# ASD2501.net
KiCad netlist of a schematic drawn in EAGLE
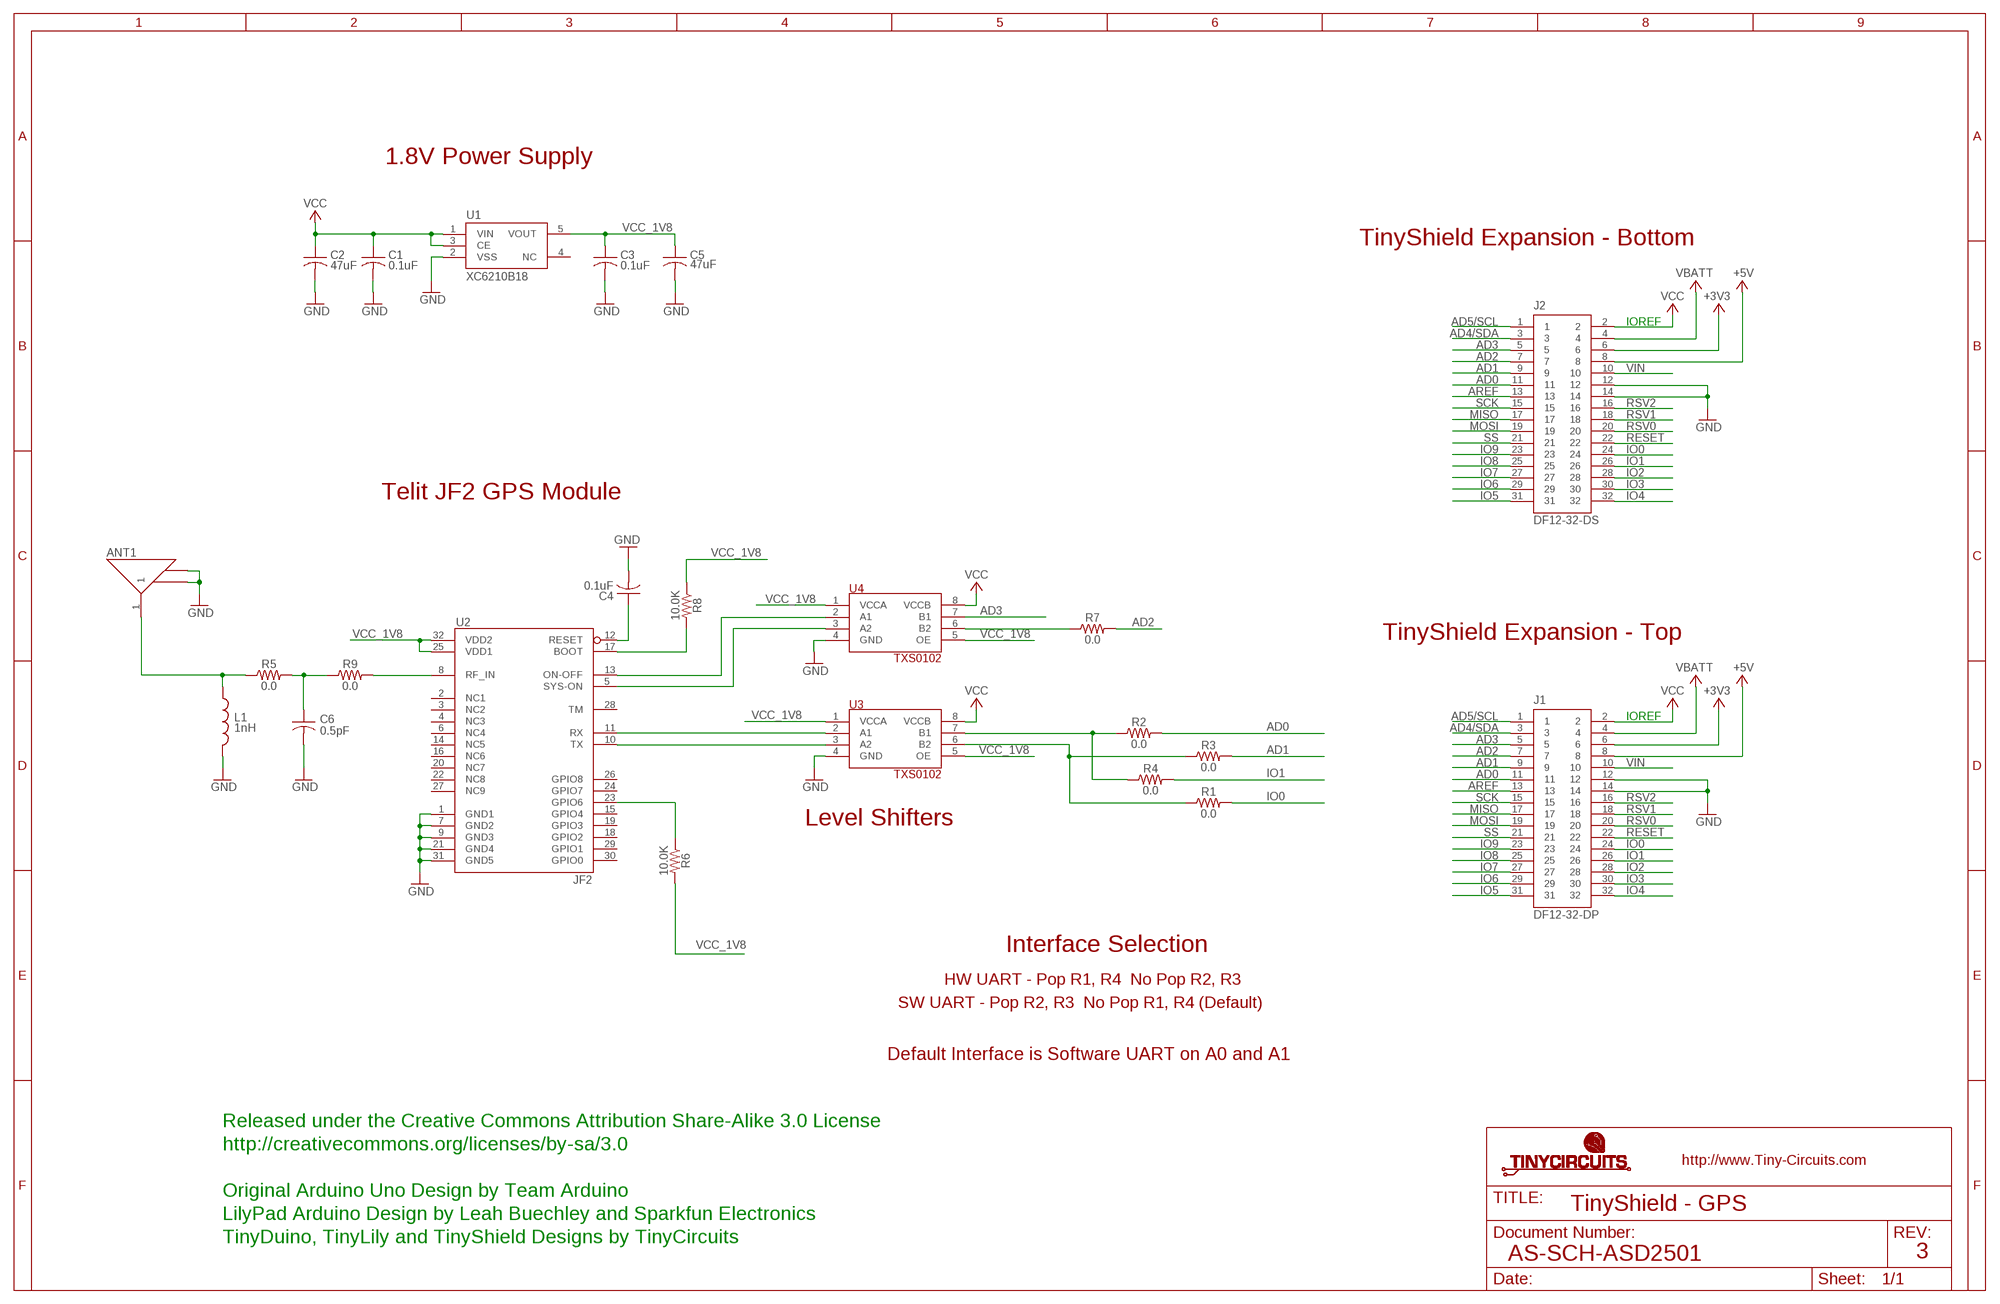
[diagram p0: schematic, sheet 1]

(export (version "E")
  (design (tool "Eeschema 10.0.6"))
  (components
    (comp (ref "ANT1")
      (value "AS-ITM-00109")
      (footprint "eagle-import:W3011")
      (libsource (lib "eagle-import") (part "AS-ITM-00109"))
    )
    (comp (ref "C1")
      (value "0.1uF")
      (footprint "eagle-import:C0402")
      (fields (field (name "PARTNO") "AS-ITM-00008") (field (name "PARTNO_1") "AS-ITM-00008"))
      (libsource (lib "eagle-import") (part "AS-ITM-00008"))
    )
    (comp (ref "C2")
      (value "47uF")
      (footprint "eagle-import:C1206")
      (fields (field (name "PARTNUM") "AS-ITM-00049") (field (name "PARTNUM_1") "AS-ITM-00049"))
      (libsource (lib "eagle-import") (part "AS-ITM-00049"))
    )
    (comp (ref "C3")
      (value "0.1uF")
      (footprint "eagle-import:C0402")
      (fields (field (name "PARTNO") "AS-ITM-00008") (field (name "PARTNO_1") "AS-ITM-00008"))
      (libsource (lib "eagle-import") (part "AS-ITM-00008"))
    )
    (comp (ref "C4")
      (value "0.1uF")
      (footprint "eagle-import:C0402")
      (fields (field (name "PARTNO") "AS-ITM-00008") (field (name "PARTNO_1") "AS-ITM-00008"))
      (libsource (lib "eagle-import") (part "AS-ITM-00008"))
    )
    (comp (ref "C5")
      (value "47uF")
      (footprint "eagle-import:C1206")
      (fields (field (name "PARTNUM") "AS-ITM-00049"))
      (libsource (lib "eagle-import") (part "AS-ITM-00049"))
    )
    (comp (ref "C6")
      (value "0.5pF")
      (footprint "eagle-import:C0402")
      (libsource (lib "eagle-import") (part "AS-ITM-00126"))
    )
    (comp (ref "J1")
      (value "DF12-32-DP")
      (footprint "eagle-import:DF12-32-DP")
      (fields (field (name "PARTNO") "AS-ITM-00015") (field (name "PARTNO_1") "AS-ITM-00015"))
      (libsource (lib "eagle-import") (part "AS-ITM-00015"))
    )
    (comp (ref "J2")
      (value "DF12-32-DS")
      (footprint "eagle-import:DF12-32-DS")
      (fields (field (name "PARTNO") "AS-ITM-00012") (field (name "PARTNO_1") "AS-ITM-00012"))
      (libsource (lib "eagle-import") (part "AS-ITM-00012"))
    )
    (comp (ref "L1")
      (value "1nH")
      (footprint "eagle-import:0402")
      (libsource (lib "eagle-import") (part "AS-ITM-00127"))
    )
    (comp (ref "R1")
      (value "0.0")
      (footprint "eagle-import:0402")
      (fields (field (name "PARTNO") "AS-ITM-00076"))
      (libsource (lib "eagle-import") (part "AS-ITM-00076"))
    )
    (comp (ref "R2")
      (value "0.0")
      (footprint "eagle-import:0402_SHORT")
      (libsource (lib "eagle-import") (part "AS-ITM-000760402_SHORT"))
    )
    (comp (ref "R3")
      (value "0.0")
      (footprint "eagle-import:0402_SHORT")
      (libsource (lib "eagle-import") (part "AS-ITM-000760402_SHORT"))
    )
    (comp (ref "R4")
      (value "0.0")
      (footprint "eagle-import:0402")
      (fields (field (name "PARTNO") "AS-ITM-00076"))
      (libsource (lib "eagle-import") (part "AS-ITM-00076"))
    )
    (comp (ref "R5")
      (value "0.0")
      (footprint "eagle-import:0402")
      (fields (field (name "PARTNO") "AS-ITM-00076"))
      (libsource (lib "eagle-import") (part "AS-ITM-00076"))
    )
    (comp (ref "R6")
      (value "10.0K")
      (footprint "eagle-import:0402")
      (fields (field (name "PARTNO") "AS-ITM-00032"))
      (libsource (lib "eagle-import") (part "AS-ITM-00032"))
    )
    (comp (ref "R7")
      (value "0.0")
      (footprint "eagle-import:0402")
      (fields (field (name "PARTNO") "AS-ITM-00076") (field (name "PARTNO_1") "AS-ITM-00076"))
      (libsource (lib "eagle-import") (part "AS-ITM-00076"))
    )
    (comp (ref "R8")
      (value "10.0K")
      (footprint "eagle-import:0402")
      (fields (field (name "PARTNO") "AS-ITM-00032") (field (name "PARTNO_1") "AS-ITM-00032"))
      (libsource (lib "eagle-import") (part "AS-ITM-00032"))
    )
    (comp (ref "R9")
      (value "0.0")
      (footprint "eagle-import:0402")
      (fields (field (name "PARTNO") "AS-ITM-00076"))
      (libsource (lib "eagle-import") (part "AS-ITM-00076"))
    )
    (comp (ref "U1")
      (value "XC6210B18")
      (footprint "eagle-import:SOT-25")
      (fields (field (name "PARTNO") "AS-ITM-00075") (field (name "PARTNO_1") "AS-ITM-00075"))
      (libsource (lib "eagle-import") (part "AS-ITM-00075"))
    )
    (comp (ref "U2")
      (value "JF2")
      (footprint "eagle-import:JF2")
      (fields (field (name "PARTNO") "AS-ITM-00077"))
      (libsource (lib "eagle-import") (part "AS-ITM-00077"))
    )
    (comp (ref "U3")
      (value "TXS0102")
      (footprint "eagle-import:DQE(R-PX2SON-N8)")
      (fields (field (name "PARTNO") "AS-ITM-00073"))
      (libsource (lib "eagle-import") (part "AS-ITM-00073"))
    )
    (comp (ref "U4")
      (value "TXS0102")
      (footprint "eagle-import:DQE(R-PX2SON-N8)")
      (fields (field (name "PARTNO") "AS-ITM-00073") (field (name "PARTNO_1") "AS-ITM-00073"))
      (libsource (lib "eagle-import") (part "AS-ITM-00073"))
    )
  )
  (nets
    (net (code "1") (name "+3V3") (class "Default")
      (node (ref "J1") (pin "6") (pinfunction "6_6") (pintype "bidirectional"))
      (node (ref "J2") (pin "6") (pinfunction "6_6") (pintype "bidirectional"))
    )
    (net (code "2") (name "+5V") (class "Default")
      (node (ref "J1") (pin "8") (pinfunction "8_8") (pintype "bidirectional"))
      (node (ref "J2") (pin "8") (pinfunction "8_8") (pintype "bidirectional"))
    )
    (net (code "3") (name "/AD0") (class "Default")
      (node (ref "J1") (pin "11") (pinfunction "11_11") (pintype "bidirectional"))
      (node (ref "J2") (pin "11") (pinfunction "11_11") (pintype "bidirectional"))
      (node (ref "R2") (pin "2") (pinfunction "2_2") (pintype "passive"))
    )
    (net (code "4") (name "/AD1") (class "Default")
      (node (ref "J1") (pin "9") (pinfunction "9_9") (pintype "bidirectional"))
      (node (ref "J2") (pin "9") (pinfunction "9_9") (pintype "bidirectional"))
      (node (ref "R3") (pin "2") (pinfunction "2_2") (pintype "passive"))
    )
    (net (code "5") (name "/AD2") (class "Default")
      (node (ref "J1") (pin "7") (pinfunction "7_7") (pintype "bidirectional"))
      (node (ref "J2") (pin "7") (pinfunction "7_7") (pintype "bidirectional"))
      (node (ref "R7") (pin "2") (pinfunction "2_2") (pintype "passive"))
    )
    (net (code "6") (name "/AD3") (class "Default")
      (node (ref "J1") (pin "5") (pinfunction "5_5") (pintype "bidirectional"))
      (node (ref "J2") (pin "5") (pinfunction "5_5") (pintype "bidirectional"))
      (node (ref "U4") (pin "7") (pinfunction "B1_7") (pintype "bidirectional"))
    )
    (net (code "7") (name "/AD4{slash}SDA") (class "Default")
      (node (ref "J1") (pin "3") (pinfunction "3_3") (pintype "bidirectional"))
      (node (ref "J2") (pin "3") (pinfunction "3_3") (pintype "bidirectional"))
    )
    (net (code "8") (name "/AD5{slash}SCL") (class "Default")
      (node (ref "J1") (pin "1") (pinfunction "1_1") (pintype "bidirectional"))
      (node (ref "J2") (pin "1") (pinfunction "1_1") (pintype "bidirectional"))
    )
    (net (code "9") (name "/AREF") (class "Default")
      (node (ref "J1") (pin "13") (pinfunction "13_13") (pintype "bidirectional"))
      (node (ref "J2") (pin "13") (pinfunction "13_13") (pintype "bidirectional"))
    )
    (net (code "10") (name "/IO0") (class "Default")
      (node (ref "J1") (pin "24") (pinfunction "24_24") (pintype "bidirectional"))
      (node (ref "J2") (pin "24") (pinfunction "24_24") (pintype "bidirectional"))
      (node (ref "R1") (pin "2") (pinfunction "2_2") (pintype "passive"))
    )
    (net (code "11") (name "/IO1") (class "Default")
      (node (ref "J1") (pin "26") (pinfunction "26_26") (pintype "bidirectional"))
      (node (ref "J2") (pin "26") (pinfunction "26_26") (pintype "bidirectional"))
      (node (ref "R4") (pin "2") (pinfunction "2_2") (pintype "passive"))
    )
    (net (code "12") (name "/IO2") (class "Default")
      (node (ref "J1") (pin "28") (pinfunction "28_28") (pintype "bidirectional"))
      (node (ref "J2") (pin "28") (pinfunction "28_28") (pintype "bidirectional"))
    )
    (net (code "13") (name "/IO3") (class "Default")
      (node (ref "J1") (pin "30") (pinfunction "30_30") (pintype "bidirectional"))
      (node (ref "J2") (pin "30") (pinfunction "30_30") (pintype "bidirectional"))
    )
    (net (code "14") (name "/IO4") (class "Default")
      (node (ref "J1") (pin "32") (pinfunction "32_32") (pintype "bidirectional"))
      (node (ref "J2") (pin "32") (pinfunction "32_32") (pintype "bidirectional"))
    )
    (net (code "15") (name "/IO5") (class "Default")
      (node (ref "J1") (pin "31") (pinfunction "31_31") (pintype "bidirectional"))
      (node (ref "J2") (pin "31") (pinfunction "31_31") (pintype "bidirectional"))
    )
    (net (code "16") (name "/IO6") (class "Default")
      (node (ref "J1") (pin "29") (pinfunction "29_29") (pintype "bidirectional"))
      (node (ref "J2") (pin "29") (pinfunction "29_29") (pintype "bidirectional"))
    )
    (net (code "17") (name "/IO7") (class "Default")
      (node (ref "J1") (pin "27") (pinfunction "27_27") (pintype "bidirectional"))
      (node (ref "J2") (pin "27") (pinfunction "27_27") (pintype "bidirectional"))
    )
    (net (code "18") (name "/IO8") (class "Default")
      (node (ref "J1") (pin "25") (pinfunction "25_25") (pintype "bidirectional"))
      (node (ref "J2") (pin "25") (pinfunction "25_25") (pintype "bidirectional"))
    )
    (net (code "19") (name "/IO9") (class "Default")
      (node (ref "J1") (pin "23") (pinfunction "23_23") (pintype "bidirectional"))
      (node (ref "J2") (pin "23") (pinfunction "23_23") (pintype "bidirectional"))
    )
    (net (code "20") (name "/MISO") (class "Default")
      (node (ref "J1") (pin "17") (pinfunction "17_17") (pintype "bidirectional"))
      (node (ref "J2") (pin "17") (pinfunction "17_17") (pintype "bidirectional"))
    )
    (net (code "21") (name "/MOSI") (class "Default")
      (node (ref "J1") (pin "19") (pinfunction "19_19") (pintype "bidirectional"))
      (node (ref "J2") (pin "19") (pinfunction "19_19") (pintype "bidirectional"))
    )
    (net (code "22") (name "/RESET") (class "Default")
      (node (ref "J1") (pin "22") (pinfunction "22_22") (pintype "bidirectional"))
      (node (ref "J2") (pin "22") (pinfunction "22_22") (pintype "bidirectional"))
    )
    (net (code "23") (name "/RSV0") (class "Default")
      (node (ref "J1") (pin "20") (pinfunction "20_20") (pintype "bidirectional"))
      (node (ref "J2") (pin "20") (pinfunction "20_20") (pintype "bidirectional"))
    )
    (net (code "24") (name "/RSV1") (class "Default")
      (node (ref "J1") (pin "18") (pinfunction "18_18") (pintype "bidirectional"))
      (node (ref "J2") (pin "18") (pinfunction "18_18") (pintype "bidirectional"))
    )
    (net (code "25") (name "/RSV2") (class "Default")
      (node (ref "J1") (pin "16") (pinfunction "16_16") (pintype "bidirectional"))
      (node (ref "J2") (pin "16") (pinfunction "16_16") (pintype "bidirectional"))
    )
    (net (code "26") (name "/SCK") (class "Default")
      (node (ref "J1") (pin "15") (pinfunction "15_15") (pintype "bidirectional"))
      (node (ref "J2") (pin "15") (pinfunction "15_15") (pintype "bidirectional"))
    )
    (net (code "27") (name "/SS") (class "Default")
      (node (ref "J1") (pin "21") (pinfunction "21_21") (pintype "bidirectional"))
      (node (ref "J2") (pin "21") (pinfunction "21_21") (pintype "bidirectional"))
    )
    (net (code "28") (name "/VCC_1V8") (class "Default")
      (node (ref "C3") (pin "1") (pinfunction "1_1") (pintype "passive"))
      (node (ref "C5") (pin "1") (pinfunction "1_1") (pintype "passive"))
      (node (ref "R6") (pin "2") (pinfunction "2_2") (pintype "passive"))
      (node (ref "R8") (pin "1") (pinfunction "1_1") (pintype "passive"))
      (node (ref "U1") (pin "5") (pinfunction "VOUT_5") (pintype "bidirectional"))
      (node (ref "U2") (pin "25") (pinfunction "VDD1_25") (pintype "power_in"))
      (node (ref "U2") (pin "32") (pinfunction "VDD2_32") (pintype "power_in"))
      (node (ref "U3") (pin "1") (pinfunction "VCCA_1") (pintype "bidirectional"))
      (node (ref "U3") (pin "5") (pinfunction "OE_5") (pintype "bidirectional"))
      (node (ref "U4") (pin "1") (pinfunction "VCCA_1") (pintype "bidirectional"))
      (node (ref "U4") (pin "5") (pinfunction "OE_5") (pintype "bidirectional"))
    )
    (net (code "29") (name "/VIN") (class "Default")
      (node (ref "J1") (pin "10") (pinfunction "10_10") (pintype "bidirectional"))
      (node (ref "J2") (pin "10") (pinfunction "10_10") (pintype "bidirectional"))
    )
    (net (code "30") (name "GND") (class "Default")
      (node (ref "ANT1") (pin "2") (pinfunction "G1_2") (pintype "bidirectional"))
      (node (ref "ANT1") (pin "3") (pinfunction "G2_3") (pintype "bidirectional"))
      (node (ref "C1") (pin "2") (pinfunction "2_2") (pintype "passive"))
      (node (ref "C2") (pin "2") (pinfunction "2_2") (pintype "passive"))
      (node (ref "C3") (pin "2") (pinfunction "2_2") (pintype "passive"))
      (node (ref "C4") (pin "2") (pinfunction "2_2") (pintype "passive"))
      (node (ref "C5") (pin "2") (pinfunction "2_2") (pintype "passive"))
      (node (ref "C6") (pin "2") (pinfunction "2_2") (pintype "passive"))
      (node (ref "J1") (pin "12") (pinfunction "12_12") (pintype "bidirectional"))
      (node (ref "J1") (pin "14") (pinfunction "14_14") (pintype "bidirectional"))
      (node (ref "J2") (pin "12") (pinfunction "12_12") (pintype "bidirectional"))
      (node (ref "J2") (pin "14") (pinfunction "14_14") (pintype "bidirectional"))
      (node (ref "L1") (pin "2") (pinfunction "2_2") (pintype "passive"))
      (node (ref "U1") (pin "2") (pinfunction "VSS_2") (pintype "power_in"))
      (node (ref "U2") (pin "1") (pinfunction "GND1_1") (pintype "power_in"))
      (node (ref "U2") (pin "21") (pinfunction "GND4_21") (pintype "power_in"))
      (node (ref "U2") (pin "31") (pinfunction "GND5_31") (pintype "power_in"))
      (node (ref "U2") (pin "7") (pinfunction "GND2_7") (pintype "power_in"))
      (node (ref "U2") (pin "9") (pinfunction "GND3_9") (pintype "power_in"))
      (node (ref "U3") (pin "4") (pinfunction "GND_4") (pintype "bidirectional"))
      (node (ref "U4") (pin "4") (pinfunction "GND_4") (pintype "bidirectional"))
    )
    (net (code "31") (name "Net-(ANT1-Pad1)") (class "Default")
      (node (ref "ANT1") (pin "1") (pinfunction "1_1") (pintype "bidirectional"))
      (node (ref "L1") (pin "1") (pinfunction "1_1") (pintype "passive"))
      (node (ref "R5") (pin "1") (pinfunction "1_1") (pintype "passive"))
    )
    (net (code "32") (name "Net-(C6-Pad1)") (class "Default")
      (node (ref "C6") (pin "1") (pinfunction "1_1") (pintype "passive"))
      (node (ref "R5") (pin "2") (pinfunction "2_2") (pintype "passive"))
      (node (ref "R9") (pin "1") (pinfunction "1_1") (pintype "passive"))
    )
    (net (code "33") (name "Net-(U2-BOOT)") (class "Default")
      (node (ref "R8") (pin "2") (pinfunction "2_2") (pintype "passive"))
      (node (ref "U2") (pin "17") (pinfunction "BOOT_17") (pintype "bidirectional"))
    )
    (net (code "34") (name "Net-(U2-GPIO6)") (class "Default")
      (node (ref "R6") (pin "1") (pinfunction "1_1") (pintype "passive"))
      (node (ref "U2") (pin "23") (pinfunction "GPIO6_23") (pintype "bidirectional"))
    )
    (net (code "35") (name "Net-(U2-ON-OFF)") (class "Default")
      (node (ref "U2") (pin "13") (pinfunction "ON-OFF_13") (pintype "bidirectional"))
      (node (ref "U4") (pin "2") (pinfunction "A1_2") (pintype "bidirectional"))
    )
    (net (code "36") (name "Net-(U2-RESET)") (class "Default")
      (node (ref "C4") (pin "1") (pinfunction "1_1") (pintype "passive"))
      (node (ref "U2") (pin "12") (pinfunction "RESET_12") (pintype "bidirectional"))
    )
    (net (code "37") (name "Net-(U2-RF_IN)") (class "Default")
      (node (ref "R9") (pin "2") (pinfunction "2_2") (pintype "passive"))
      (node (ref "U2") (pin "8") (pinfunction "RF_IN_8") (pintype "bidirectional"))
    )
    (net (code "38") (name "Net-(U2-RX)") (class "Default")
      (node (ref "U2") (pin "11") (pinfunction "RX_11") (pintype "bidirectional"))
      (node (ref "U3") (pin "2") (pinfunction "A1_2") (pintype "bidirectional"))
    )
    (net (code "39") (name "Net-(U2-SYS-ON)") (class "Default")
      (node (ref "U2") (pin "5") (pinfunction "SYS-ON_5") (pintype "bidirectional"))
      (node (ref "U4") (pin "3") (pinfunction "A2_3") (pintype "bidirectional"))
    )
    (net (code "40") (name "Net-(U2-TX)") (class "Default")
      (node (ref "U2") (pin "10") (pinfunction "TX_10") (pintype "bidirectional"))
      (node (ref "U3") (pin "3") (pinfunction "A2_3") (pintype "bidirectional"))
    )
    (net (code "41") (name "Net-(U3-B1)") (class "Default")
      (node (ref "R2") (pin "1") (pinfunction "1_1") (pintype "passive"))
      (node (ref "R4") (pin "1") (pinfunction "1_1") (pintype "passive"))
      (node (ref "U3") (pin "7") (pinfunction "B1_7") (pintype "bidirectional"))
    )
    (net (code "42") (name "Net-(U3-B2)") (class "Default")
      (node (ref "R1") (pin "1") (pinfunction "1_1") (pintype "passive"))
      (node (ref "R3") (pin "1") (pinfunction "1_1") (pintype "passive"))
      (node (ref "U3") (pin "6") (pinfunction "B2_6") (pintype "bidirectional"))
    )
    (net (code "43") (name "Net-(U4-B2)") (class "Default")
      (node (ref "R7") (pin "1") (pinfunction "1_1") (pintype "passive"))
      (node (ref "U4") (pin "6") (pinfunction "B2_6") (pintype "bidirectional"))
    )
    (net (code "44") (name "VBATT") (class "Default")
      (node (ref "J1") (pin "4") (pinfunction "4_4") (pintype "bidirectional"))
      (node (ref "J2") (pin "4") (pinfunction "4_4") (pintype "bidirectional"))
    )
    (net (code "45") (name "VCC") (class "Default")
      (node (ref "C1") (pin "1") (pinfunction "1_1") (pintype "passive"))
      (node (ref "C2") (pin "1") (pinfunction "1_1") (pintype "passive"))
      (node (ref "J1") (pin "2") (pinfunction "2_2") (pintype "bidirectional"))
      (node (ref "J2") (pin "2") (pinfunction "2_2") (pintype "bidirectional"))
      (node (ref "U1") (pin "1") (pinfunction "VIN_1") (pintype "bidirectional"))
      (node (ref "U1") (pin "3") (pinfunction "CE_3") (pintype "bidirectional"))
      (node (ref "U3") (pin "8") (pinfunction "VCCB_8") (pintype "bidirectional"))
      (node (ref "U4") (pin "8") (pinfunction "VCCB_8") (pintype "bidirectional"))
    )
    (net (code "46") (name "unconnected-(U1-NC-Pad4)") (class "Default")
      (node (ref "U1") (pin "4") (pinfunction "NC_4") (pintype "bidirectional"))
    )
    (net (code "47") (name "unconnected-(U2-GPIO0-Pad30)") (class "Default")
      (node (ref "U2") (pin "30") (pinfunction "GPIO0_30") (pintype "bidirectional"))
    )
    (net (code "48") (name "unconnected-(U2-GPIO1-Pad29)") (class "Default")
      (node (ref "U2") (pin "29") (pinfunction "GPIO1_29") (pintype "bidirectional"))
    )
    (net (code "49") (name "unconnected-(U2-GPIO2-Pad18)") (class "Default")
      (node (ref "U2") (pin "18") (pinfunction "GPIO2_18") (pintype "bidirectional"))
    )
    (net (code "50") (name "unconnected-(U2-GPIO3-Pad19)") (class "Default")
      (node (ref "U2") (pin "19") (pinfunction "GPIO3_19") (pintype "bidirectional"))
    )
    (net (code "51") (name "unconnected-(U2-GPIO4-Pad15)") (class "Default")
      (node (ref "U2") (pin "15") (pinfunction "GPIO4_15") (pintype "bidirectional"))
    )
    (net (code "52") (name "unconnected-(U2-GPIO7-Pad24)") (class "Default")
      (node (ref "U2") (pin "24") (pinfunction "GPIO7_24") (pintype "bidirectional"))
    )
    (net (code "53") (name "unconnected-(U2-GPIO8-Pad26)") (class "Default")
      (node (ref "U2") (pin "26") (pinfunction "GPIO8_26") (pintype "bidirectional"))
    )
    (net (code "54") (name "unconnected-(U2-NC1-Pad2)") (class "Default")
      (node (ref "U2") (pin "2") (pinfunction "NC1_2") (pintype "bidirectional"))
    )
    (net (code "55") (name "unconnected-(U2-NC2-Pad3)") (class "Default")
      (node (ref "U2") (pin "3") (pinfunction "NC2_3") (pintype "bidirectional"))
    )
    (net (code "56") (name "unconnected-(U2-NC3-Pad4)") (class "Default")
      (node (ref "U2") (pin "4") (pinfunction "NC3_4") (pintype "bidirectional"))
    )
    (net (code "57") (name "unconnected-(U2-NC4-Pad6)") (class "Default")
      (node (ref "U2") (pin "6") (pinfunction "NC4_6") (pintype "bidirectional"))
    )
    (net (code "58") (name "unconnected-(U2-NC5-Pad14)") (class "Default")
      (node (ref "U2") (pin "14") (pinfunction "NC5_14") (pintype "bidirectional"))
    )
    (net (code "59") (name "unconnected-(U2-NC6-Pad16)") (class "Default")
      (node (ref "U2") (pin "16") (pinfunction "NC6_16") (pintype "bidirectional"))
    )
    (net (code "60") (name "unconnected-(U2-NC7-Pad20)") (class "Default")
      (node (ref "U2") (pin "20") (pinfunction "NC7_20") (pintype "bidirectional"))
    )
    (net (code "61") (name "unconnected-(U2-NC8-Pad22)") (class "Default")
      (node (ref "U2") (pin "22") (pinfunction "NC8_22") (pintype "bidirectional"))
    )
    (net (code "62") (name "unconnected-(U2-NC9-Pad27)") (class "Default")
      (node (ref "U2") (pin "27") (pinfunction "NC9_27") (pintype "bidirectional"))
    )
    (net (code "63") (name "unconnected-(U2-TM-Pad28)") (class "Default")
      (node (ref "U2") (pin "28") (pinfunction "TM_28") (pintype "bidirectional"))
    )
  )
)
